# ProPrj_PiezoBuds-final_2024-09-30.net
KiCad netlist of a schematic drawn in EasyEDA Pro
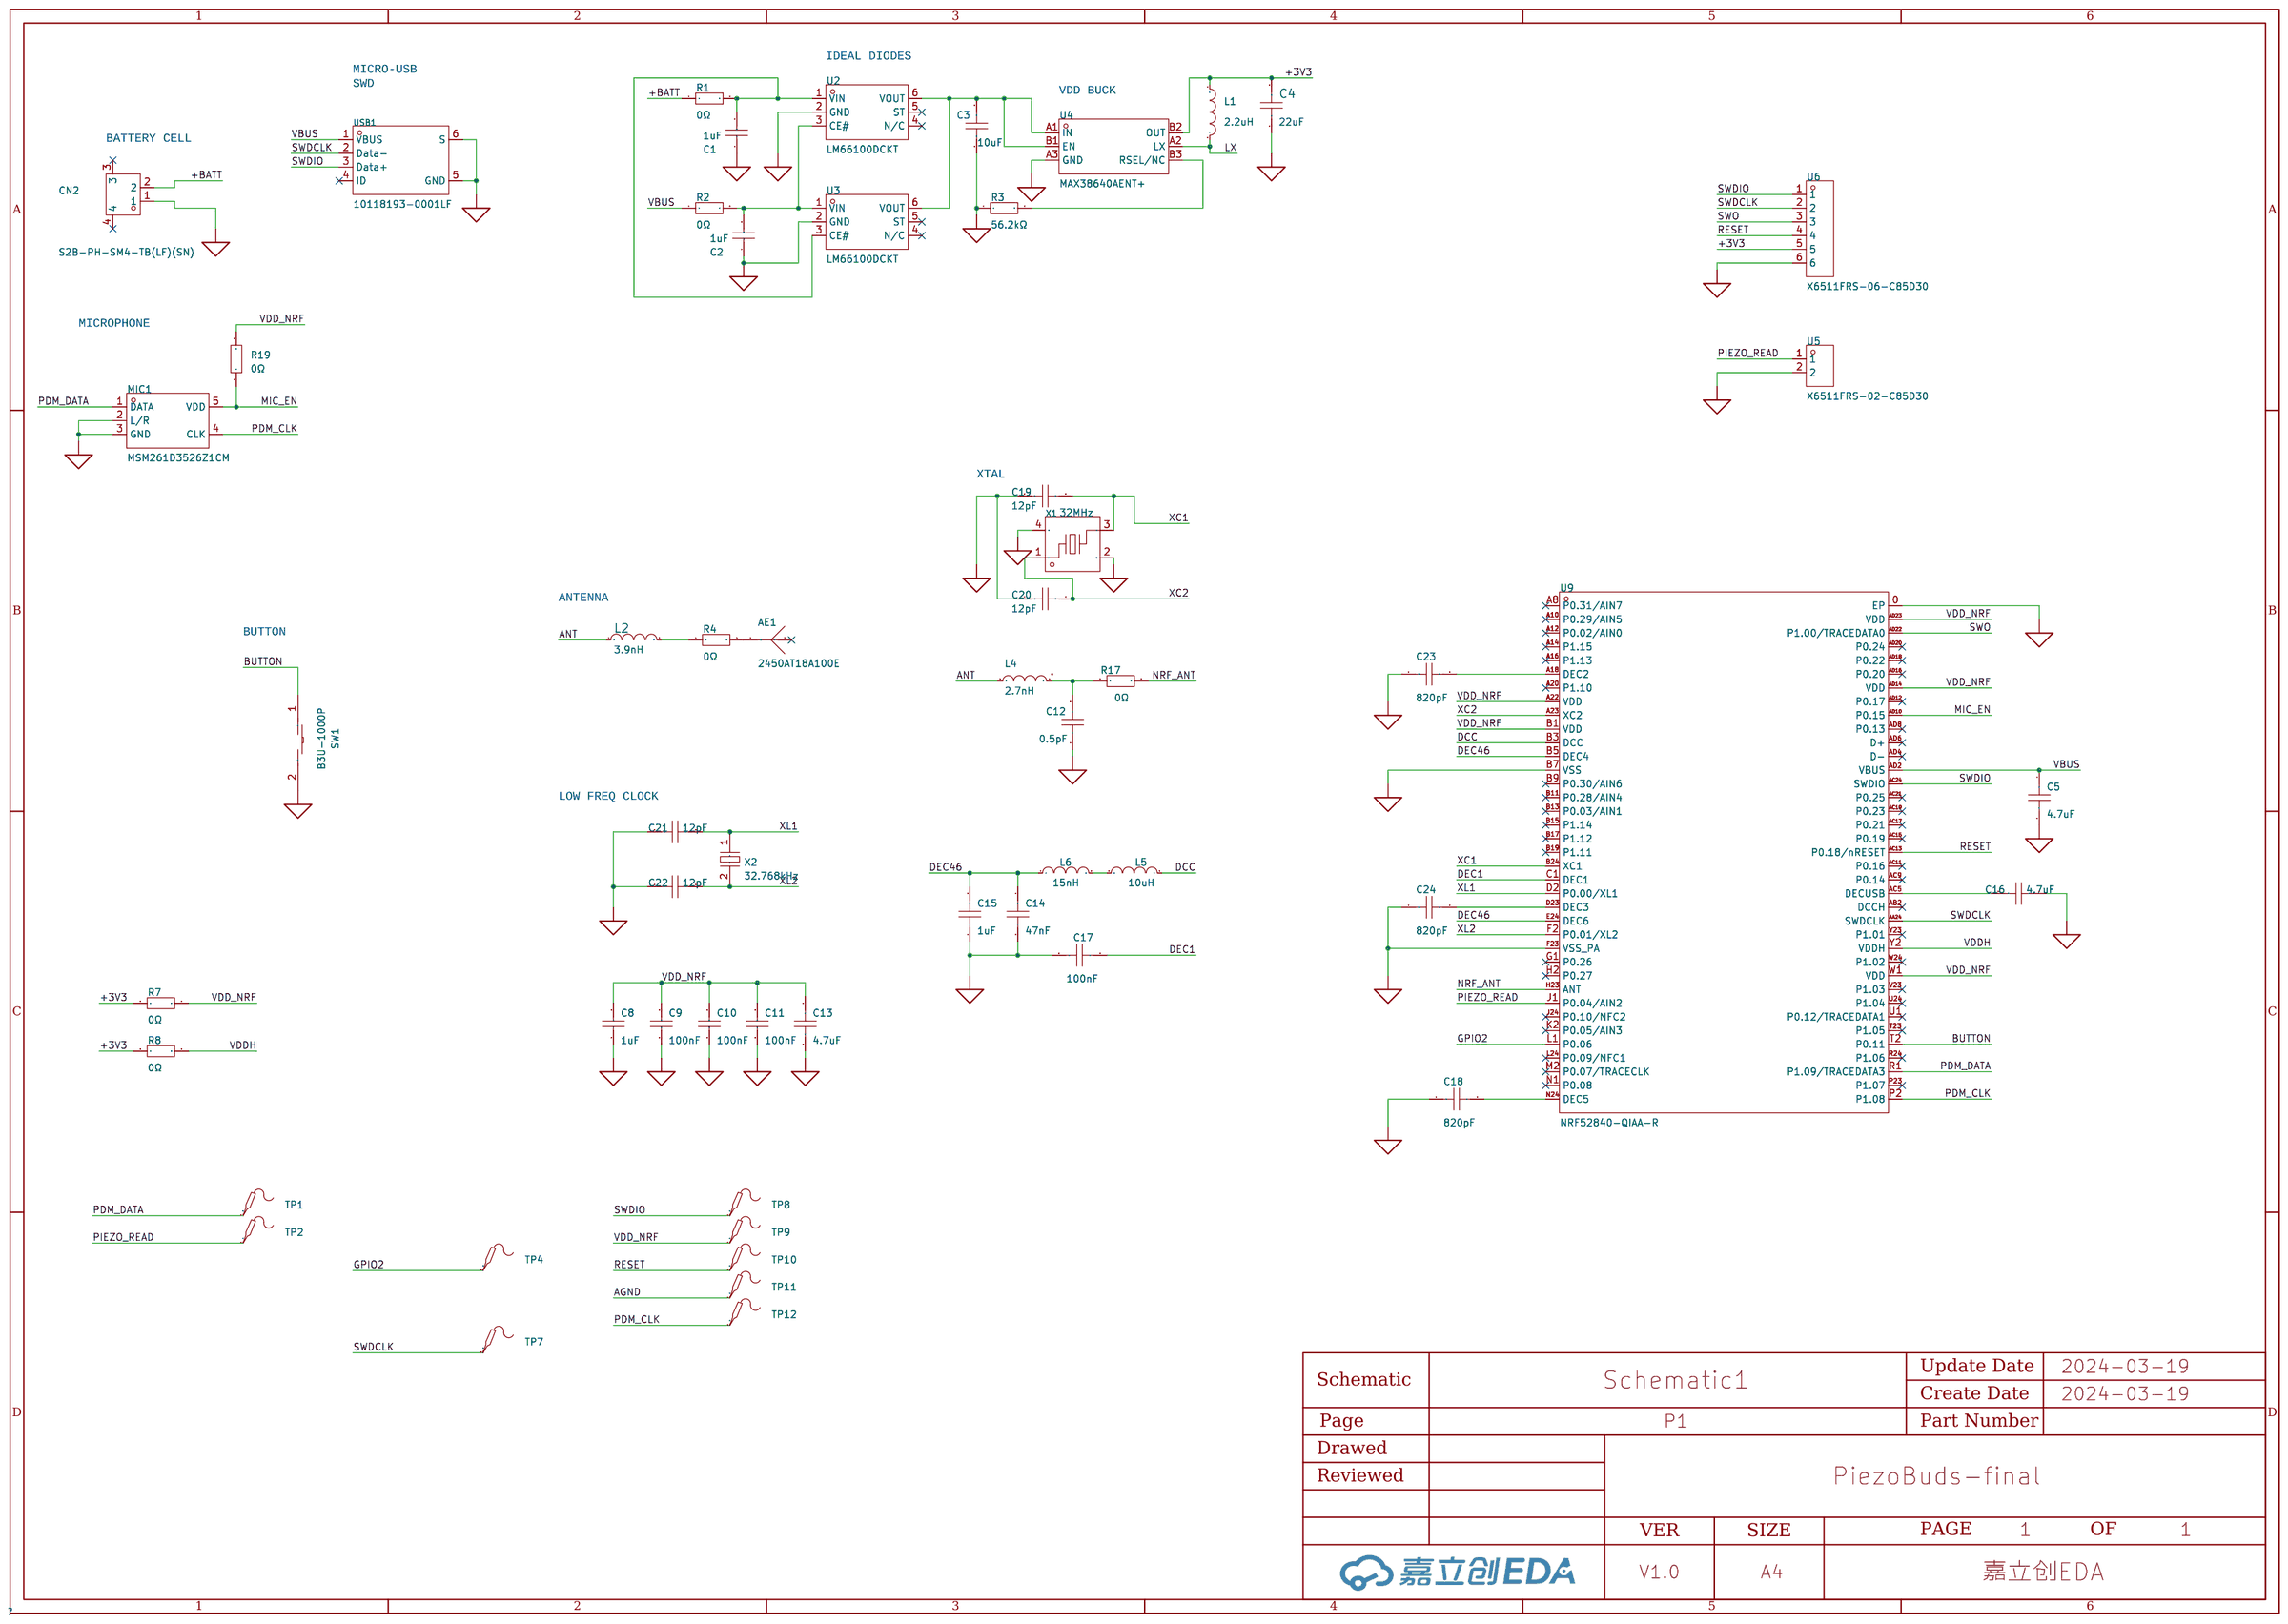
[diagram p0: schematic sheet]

(export (version "E")
  (design (tool "Eeschema 10.0.6"))
  (components
    (comp (ref "AE1")
      (value "2450AT18A100E")
      (footprint "easyedapro:ANT-SMD_L3.2-W1.6")
      (description "天线类型:迷你2.45 GHz天线;中心频点:2.4GHz;带宽:-;峰值增益:0.5dBi;驻波比:-;极化方式:-;阻抗:50Ω;功率容量:2W;")
      (fields (field (name "Manufacturer") "JOHANSON(约翰逊)"))
      (libsource (lib "easyedapro") (part "2450AT18A100E"))
    )
    (comp (ref "C1")
      (value "1uF")
      (footprint "easyedapro:C0402")
      (description "容值:1uF;精度:±10%;额定电压:6.3V;材质(温度系数):X5R;")
      (fields
        (field (name "Manufacturer Part") "CL05A105KQ5NNNC")
        (field (name "Manufacturer") "SAMSUNG(三星)")
      )
      (libsource (lib "easyedapro") (part "CL05A105KQ5NNNC"))
    )
    (comp (ref "C2")
      (value "1uF")
      (footprint "easyedapro:C0402")
      (description "容值:1uF;精度:±10%;额定电压:6.3V;材质(温度系数):X5R;")
      (fields
        (field (name "Manufacturer Part") "CL05A105KQ5NNNC")
        (field (name "Manufacturer") "SAMSUNG(三星)")
      )
      (libsource (lib "easyedapro") (part "CL05A105KQ5NNNC"))
    )
    (comp (ref "C3")
      (value "10uF")
      (footprint "easyedapro:C0402")
      (description "容值:10uF;精度:±20%;额定电压:10V;材质(温度系数):X5R;")
      (fields
        (field (name "Manufacturer Part") "CL05A106MP5NUNC")
        (field (name "Manufacturer") "SAMSUNG(三星)")
      )
      (libsource (lib "easyedapro") (part "CL05A106MP5NUNC_C315248"))
    )
    (comp (ref "C4")
      (value "22uF")
      (footprint "easyedapro:C0402")
      (description "容值:22uF;精度:±20%;额定电压:6.3V;材质(温度系数):X5R;")
      (fields
        (field (name "Manufacturer Part") "GRM155R60J226ME11D")
        (field (name "Manufacturer") "muRata(村田)")
      )
      (libsource (lib "easyedapro") (part "GRM155R60J226ME11D"))
    )
    (comp (ref "C5")
      (value "4.7uF")
      (footprint "easyedapro:C0402")
      (description "容值:4.7uF;精度:±20%;额定电压:4V;材质(温度系数):X6S;")
      (fields (field (name "Manufacturer Part") "C1005X6S0G475M050BC") (field (name "Manufacturer") "TDK"))
      (libsource (lib "easyedapro") (part "C1005X6S0G475M050BC"))
    )
    (comp (ref "C8")
      (value "1uF")
      (footprint "easyedapro:C0402")
      (description "容值:1uF;精度:±10%;额定电压:6.3V;材质(温度系数):X5R;")
      (fields
        (field (name "Manufacturer Part") "CL05A105KQ5NNNC")
        (field (name "Manufacturer") "SAMSUNG(三星)")
      )
      (libsource (lib "easyedapro") (part "CL05A105KQ5NNNC"))
    )
    (comp (ref "C9")
      (value "100nF")
      (footprint "easyedapro:C0201")
      (description "容值:100nF;精度:±10%;额定电压:16V;材质(温度系数):X7S;")
      (fields
        (field (name "Manufacturer Part") "GRM033C71C104KE14D")
        (field (name "Manufacturer") "muRata(村田)")
      )
      (libsource (lib "easyedapro") (part "GRM033C71C104KE14D"))
    )
    (comp (ref "C10")
      (value "100nF")
      (footprint "easyedapro:C0201")
      (description "容值:100nF;精度:±10%;额定电压:16V;材质(温度系数):X7S;")
      (fields
        (field (name "Manufacturer Part") "GRM033C71C104KE14D")
        (field (name "Manufacturer") "muRata(村田)")
      )
      (libsource (lib "easyedapro") (part "GRM033C71C104KE14D"))
    )
    (comp (ref "C11")
      (value "100nF")
      (footprint "easyedapro:C0201")
      (description "容值:100nF;精度:±10%;额定电压:16V;材质(温度系数):X7S;")
      (fields
        (field (name "Manufacturer Part") "GRM033C71C104KE14D")
        (field (name "Manufacturer") "muRata(村田)")
      )
      (libsource (lib "easyedapro") (part "GRM033C71C104KE14D"))
    )
    (comp (ref "C12")
      (value "0.5pF")
      (footprint "easyedapro:C0201")
      (description "容值:0.5pF;额定电压:25V;材质(温度系数):C0G;")
      (fields (field (name "Manufacturer Part") "0201CG0R5B250NT") (field (name "Manufacturer") "FH(风华)"))
      (libsource (lib "easyedapro") (part "0201CG0R5B250NT"))
    )
    (comp (ref "C13")
      (value "4.7uF")
      (footprint "easyedapro:C0402")
      (description "容值:4.7uF;精度:±10%;额定电压:10V;材质(温度系数):X5R;")
      (fields
        (field (name "Manufacturer Part") "CL05A475KP5NRNC")
        (field (name "Manufacturer") "SAMSUNG(三星)")
      )
      (libsource (lib "easyedapro") (part "CL05A475KP5NRNC"))
    )
    (comp (ref "C14")
      (value "47nF")
      (footprint "easyedapro:C0201")
      (description "容值:47nF;精度:±10%;额定电压:6.3V;材质(温度系数):X5R;")
      (fields
        (field (name "Manufacturer Part") "CL03A473KQ3NNNC")
        (field (name "Manufacturer") "SAMSUNG(三星)")
      )
      (libsource (lib "easyedapro") (part "CL03A473KQ3NNNC"))
    )
    (comp (ref "C15")
      (value "1uF")
      (footprint "easyedapro:C0402")
      (description "容值:1uF;精度:±10%;额定电压:6.3V;材质(温度系数):X7R;")
      (fields
        (field (name "Manufacturer Part") "GRM155R70J105KA12D")
        (field (name "Manufacturer") "muRata(村田)")
      )
      (libsource (lib "easyedapro") (part "GRM155R70J105KA12D"))
    )
    (comp (ref "C16")
      (value "4.7uF")
      (footprint "easyedapro:C0402")
      (description "容值:4.7uF;精度:±10%;额定电压:10V;材质(温度系数):X5R;")
      (fields
        (field (name "Manufacturer Part") "CL05A475KP5NRNC")
        (field (name "Manufacturer") "SAMSUNG(三星)")
      )
      (libsource (lib "easyedapro") (part "CL05A475KP5NRNC"))
    )
    (comp (ref "C17")
      (value "100nF")
      (footprint "easyedapro:C0201")
      (description "容值:100nF;精度:±10%;额定电压:6.3V;材质(温度系数):X5R;")
      (fields
        (field (name "Manufacturer Part") "CL03A104KQ3NNNC")
        (field (name "Manufacturer") "SAMSUNG(三星)")
      )
      (libsource (lib "easyedapro") (part "CL03A104KQ3NNNC"))
    )
    (comp (ref "C18")
      (value "820pF")
      (footprint "easyedapro:C0201")
      (description "容值:820pF;精度:±5%;额定电压:25V;材质(温度系数):C0G;")
      (fields
        (field (name "Manufacturer Part") "GRM0335C1E821JA01D")
        (field (name "Manufacturer") "muRata(村田)")
      )
      (libsource (lib "easyedapro") (part "GRM0335C1E821JA01D"))
    )
    (comp (ref "C19")
      (value "12pF")
      (footprint "easyedapro:C0201")
      (description "容值:12pF;精度:±2%;额定电压:25V;材质(温度系数):C0G;")
      (fields
        (field (name "Manufacturer Part") "GRM0335C1E120GA01D")
        (field (name "Manufacturer") "muRata(村田)")
      )
      (libsource (lib "easyedapro") (part "GRM0335C1E120GA01D"))
    )
    (comp (ref "C20")
      (value "12pF")
      (footprint "easyedapro:C0201")
      (description "容值:12pF;精度:±2%;额定电压:25V;材质(温度系数):C0G;")
      (fields
        (field (name "Manufacturer Part") "GRM0335C1E120GA01D")
        (field (name "Manufacturer") "muRata(村田)")
      )
      (libsource (lib "easyedapro") (part "GRM0335C1E120GA01D"))
    )
    (comp (ref "C21")
      (value "12pF")
      (footprint "easyedapro:C0201")
      (description "容值:12pF;精度:±2%;额定电压:25V;材质(温度系数):C0G;")
      (fields
        (field (name "Manufacturer Part") "GRM0335C1E120GA01D")
        (field (name "Manufacturer") "muRata(村田)")
      )
      (libsource (lib "easyedapro") (part "GRM0335C1E120GA01D"))
    )
    (comp (ref "C22")
      (value "12pF")
      (footprint "easyedapro:C0201")
      (description "容值:12pF;精度:±2%;额定电压:25V;材质(温度系数):C0G;")
      (fields
        (field (name "Manufacturer Part") "GRM0335C1E120GA01D")
        (field (name "Manufacturer") "muRata(村田)")
      )
      (libsource (lib "easyedapro") (part "GRM0335C1E120GA01D"))
    )
    (comp (ref "C23")
      (value "820pF")
      (footprint "easyedapro:C0201")
      (description "容值:820pF;精度:±5%;额定电压:25V;材质(温度系数):C0G;")
      (fields
        (field (name "Manufacturer Part") "GRM0335C1E821JA01D")
        (field (name "Manufacturer") "muRata(村田)")
      )
      (libsource (lib "easyedapro") (part "GRM0335C1E821JA01D"))
    )
    (comp (ref "C24")
      (value "820pF")
      (footprint "easyedapro:C0201")
      (description "容值:820pF;精度:±5%;额定电压:25V;材质(温度系数):C0G;")
      (fields
        (field (name "Manufacturer Part") "GRM0335C1E821JA01D")
        (field (name "Manufacturer") "muRata(村田)")
      )
      (libsource (lib "easyedapro") (part "GRM0335C1E821JA01D"))
    )
    (comp (ref "CN2")
      (value "S2B-PH-SM4-TB(LF)(SN)")
      (footprint "easyedapro:CONN-SMD_P2.00_S2B-PH-SM4-TB-LF-SN")
      (fields (field (name "Manufacturer") "JST"))
      (libsource (lib "easyedapro") (part "S2B-PH-SM4-TB(LF)(SN)"))
    )
    (comp (ref "L1")
      (value "2.2uH")
      (footprint "easyedapro:L0603")
      (description "类型:-;电感值:2.2uH;精度:±20%;额定电流:250mA;饱和电流(Isat):-;")
      (fields
        (field (name "Manufacturer Part") "SLM16082R2MIT")
        (field (name "Manufacturer") "Sunltech(韩国顺磁)")
      )
      (libsource (lib "easyedapro") (part "SLM16082R2MIT"))
    )
    (comp (ref "L2")
      (value "3.9nH")
      (footprint "easyedapro:IND-SMD_L1.0-W0.5-2")
      (description "电感值:3.9nH;额定电流:-;饱和电流(Isat):-;直流电阻(DCR):70mΩ;")
      (fields (field (name "Manufacturer Part") "LQW15AN3N9C00D") (field (name "Manufacturer") "muRata(村田)"))
      (libsource (lib "easyedapro") (part "LQW15AN3N9C00D"))
    )
    (comp (ref "L4")
      (value "2.7nH")
      (footprint "easyedapro:L0201-RD")
      (description "电感值:2.7nH;精度:-;额定电流:450mA;饱和电流(Isat):-;直流电阻(DCR):250mΩ;")
      (fields (field (name "Manufacturer Part") "LQP03TG2N7B02D") (field (name "Manufacturer") "muRata(村田)"))
      (libsource (lib "easyedapro") (part "LQP03TG2N7B02D"))
    )
    (comp (ref "L5")
      (value "10uH")
      (footprint "easyedapro:L0603")
      (description "电感值:10uH;精度:±20%;额定电流:300mA;饱和电流(Isat):60mA;直流电阻(DCR):600mΩ;")
      (fields (field (name "Manufacturer Part") "MLZ1608N100LT000") (field (name "Manufacturer") "TDK"))
      (libsource (lib "easyedapro") (part "MLZ1608N100LT000"))
    )
    (comp (ref "L6")
      (value "15nH")
      (footprint "easyedapro:L0201")
      (description "直流电阻(DCR):700mΩ;精度:±5%;电感值:15nH;额定电流:3.8A;饱和电流(Isat):-;")
      (fields (field (name "Manufacturer Part") "LQP03TN15NJ02D") (field (name "Manufacturer") "muRata(村田)"))
      (libsource (lib "easyedapro") (part "LQP03TN15NJ02D"))
    )
    (comp (ref "MIC1")
      (value "MSM261D3526Z1CM")
      (footprint "easyedapro:OCLGA-6_L3.5-W2.7-TL-MSM261D3526Z1CM")
      (description "方向:全指向;灵敏度:-26dB；-25dB;信噪比:62dB；64dB;电流消耗:670uA；290uA;电源电压:1.8V;阻抗:-;")
      (fields (field (name "Manufacturer") "MEMS(敏芯微)"))
      (libsource (lib "easyedapro") (part "MSM261D3526Z1CM"))
    )
    (comp (ref "R1")
      (value "0Ω")
      (footprint "easyedapro:R0201")
      (description "温度系数:-;工作温度范围:-55°C~+155°C;电阻长:-;精度:±5%;电阻直径:-;电阻高:-;电阻宽:-;最大工作电压:25V;电阻类型:厚膜电阻;阻值:0Ω;功率:50mW;")
      (fields (field (name "Manufacturer Part") "RC0201JR-070RL") (field (name "Manufacturer") "YAGEO(国巨)"))
      (libsource (lib "easyedapro") (part "RC0201JR-070RL"))
    )
    (comp (ref "R2")
      (value "0Ω")
      (footprint "easyedapro:R0201")
      (description "温度系数:-;工作温度范围:-55°C~+155°C;电阻长:-;精度:±5%;电阻直径:-;电阻高:-;电阻宽:-;最大工作电压:25V;电阻类型:厚膜电阻;阻值:0Ω;功率:50mW;")
      (fields (field (name "Manufacturer Part") "RC0201JR-070RL") (field (name "Manufacturer") "YAGEO(国巨)"))
      (libsource (lib "easyedapro") (part "RC0201JR-070RL"))
    )
    (comp (ref "R3")
      (value "56.2kΩ")
      (footprint "easyedapro:R0201")
      (description "电阻类型:厚膜电阻;阻值:768kΩ;精度:±1%;功率:50mW;")
      (fields (field (name "Manufacturer Part") "RC0201FR-0756K2L") (field (name "Manufacturer") "YAGEO(国巨)"))
      (libsource (lib "easyedapro") (part "0201WMF7683TCE"))
    )
    (comp (ref "R4")
      (value "0Ω")
      (footprint "easyedapro:R0201")
      (description "温度系数:-;工作温度范围:-55°C~+155°C;电阻长:-;精度:±5%;电阻直径:-;电阻高:-;电阻宽:-;最大工作电压:25V;电阻类型:厚膜电阻;阻值:0Ω;功率:50mW;")
      (fields (field (name "Manufacturer Part") "RC0201JR-070RL") (field (name "Manufacturer") "YAGEO(国巨)"))
      (libsource (lib "easyedapro") (part "RC0201JR-070RL"))
    )
    (comp (ref "R7")
      (value "0Ω")
      (footprint "easyedapro:R0402")
      (description "电阻类型:厚膜电阻;阻值:0Ω;精度:-;功率:62.5mW;")
      (fields (field (name "Manufacturer Part") "RC0402FR-070RL") (field (name "Manufacturer") "YAGEO(国巨)"))
      (libsource (lib "easyedapro") (part "RC0402FR-070RL"))
    )
    (comp (ref "R8")
      (value "0Ω")
      (footprint "easyedapro:R0402")
      (description "电阻类型:厚膜电阻;阻值:0Ω;精度:-;功率:62.5mW;")
      (fields (field (name "Manufacturer Part") "RC0402FR-070RL") (field (name "Manufacturer") "YAGEO(国巨)"))
      (libsource (lib "easyedapro") (part "RC0402FR-070RL"))
    )
    (comp (ref "R17")
      (value "0Ω")
      (footprint "easyedapro:R0201")
      (description "温度系数:-;工作温度范围:-55°C~+155°C;电阻长:-;精度:±5%;电阻直径:-;电阻高:-;电阻宽:-;最大工作电压:25V;电阻类型:厚膜电阻;阻值:0Ω;功率:50mW;")
      (fields (field (name "Manufacturer Part") "RC0201JR-070RL") (field (name "Manufacturer") "YAGEO(国巨)"))
      (libsource (lib "easyedapro") (part "RC0201JR-070RL"))
    )
    (comp (ref "R19")
      (value "0Ω")
      (footprint "easyedapro:R0201")
      (description "温度系数:-;工作温度范围:-55°C~+155°C;电阻长:-;精度:±5%;电阻直径:-;电阻高:-;电阻宽:-;最大工作电压:25V;电阻类型:厚膜电阻;阻值:0Ω;功率:50mW;")
      (fields (field (name "Manufacturer Part") "RC0201JR-070RL") (field (name "Manufacturer") "YAGEO(国巨)"))
      (libsource (lib "easyedapro") (part "RC0201JR-070RL"))
    )
    (comp (ref "SW1")
      (value "B3U-1000P")
      (footprint "easyedapro:KEY-SMD_B3U-1000PM")
      (description "触点电流:50mA;额定电压(DC):12V;电路结构:单刀单掷;安装方式:立贴;带灯:-;机械寿命:-;")
      (fields (field (name "Manufacturer") "OMRON(欧姆龙)"))
      (libsource (lib "easyedapro") (part "B3U-1000P"))
    )
    (comp (ref "TP1")
      (value "~")
      (footprint "easyedapro:Test-Point-0.5mm")
      (description "Test Point 测试点")
      (libsource (lib "easyedapro") (part "Test-Point"))
    )
    (comp (ref "TP2")
      (value "~")
      (footprint "easyedapro:Test-Point-0.5mm")
      (description "Test Point 测试点")
      (libsource (lib "easyedapro") (part "Test-Point"))
    )
    (comp (ref "TP4")
      (value "~")
      (footprint "easyedapro:Test-Point-0.5mm")
      (description "Test Point 测试点")
      (libsource (lib "easyedapro") (part "Test-Point"))
    )
    (comp (ref "TP7")
      (value "~")
      (footprint "easyedapro:Test-Point-0.5mm")
      (description "Test Point 测试点")
      (libsource (lib "easyedapro") (part "Test-Point"))
    )
    (comp (ref "TP8")
      (value "~")
      (footprint "easyedapro:Test-Point-0.5mm")
      (description "Test Point 测试点")
      (libsource (lib "easyedapro") (part "Test-Point"))
    )
    (comp (ref "TP9")
      (value "~")
      (footprint "easyedapro:Test-Point-0.5mm")
      (description "Test Point 测试点")
      (libsource (lib "easyedapro") (part "Test-Point"))
    )
    (comp (ref "TP10")
      (value "~")
      (footprint "easyedapro:Test-Point-0.5mm")
      (description "Test Point 测试点")
      (libsource (lib "easyedapro") (part "Test-Point"))
    )
    (comp (ref "TP11")
      (value "~")
      (footprint "easyedapro:Test-Point-0.5mm")
      (description "Test Point 测试点")
      (libsource (lib "easyedapro") (part "Test-Point"))
    )
    (comp (ref "TP12")
      (value "~")
      (footprint "easyedapro:Test-Point-0.5mm")
      (description "Test Point 测试点")
      (libsource (lib "easyedapro") (part "Test-Point"))
    )
    (comp (ref "U2")
      (value "LM66100DCKT")
      (footprint "easyedapro:SC-70-6_L2.0-W1.3-P0.65-LS2.1-BL")
      (fields (field (name "Manufacturer") "TI(德州仪器)"))
      (libsource (lib "easyedapro") (part "LM66100DCKT"))
    )
    (comp (ref "U3")
      (value "LM66100DCKT")
      (footprint "easyedapro:SC-70-6_L2.0-W1.3-P0.65-LS2.1-BL")
      (fields (field (name "Manufacturer") "TI(德州仪器)"))
      (libsource (lib "easyedapro") (part "LM66100DCKT"))
    )
    (comp (ref "U4")
      (value "MAX38640AENT+")
      (footprint "easyedapro:WLP-6_L1.4-W0.9-R2-C3-P0.40-TL")
      (fields (field (name "Manufacturer") "ADI(亚德诺)"))
      (libsource (lib "easyedapro") (part "MAX38640AENT+"))
    )
    (comp (ref "U5")
      (value "X6511FRS-02-C85D30")
      (footprint "easyedapro:HDR-SMD_2P-P2.54-H-F-L11.5")
      (description "插孔结构:1x2P;间距:2.54mm;安装类型:卧贴;排数:单排;总孔位数:2P;塑高:8.5mm;")
      (fields (field (name "Manufacturer") "XKB Connectivity(中国星坤)"))
      (libsource (lib "easyedapro") (part "X6511FRS-02-C85D30"))
    )
    (comp (ref "U6")
      (value "X6511FRS-06-C85D30")
      (footprint "easyedapro:HDR-SMD_6P-P2.54-H-F-L11.5")
      (description "插孔结构:1x6P;间距:2.54mm;安装类型:卧贴;排数:单排;总孔位数:6P;塑高:8.5mm;")
      (fields (field (name "Manufacturer") "XKB Connectivity(中国星坤)"))
      (libsource (lib "easyedapro") (part "X6511FRS-06-C85D30"))
    )
    (comp (ref "U9")
      (value "NRF52840-QIAA-R")
      (footprint "easyedapro:AQFN-73_L7.0-W7.0-P0.50-BL-EP4.8")
      (fields (field (name "Manufacturer") "NORDIC"))
      (libsource (lib "easyedapro") (part "NRF52840-QIAA-R"))
    )
    (comp (ref "USB1")
      (value "10118193-0001LF")
      (footprint "easyedapro:MICRO-USB-SMD_10118193-0001LF")
      (fields (field (name "Manufacturer") "Amphenol"))
      (libsource (lib "easyedapro") (part "10118193-0001LF"))
    )
    (comp (ref "X1")
      (value "32MHz")
      (footprint "easyedapro:CRYSTAL-SMD_4P-L2.0-W1.6-BL")
      (description "晶振类型:贴片晶振;频率:32MHz;常温频差:±10ppm;外接负载电容:8pF;")
      (fields (field (name "Manufacturer Part") "Q22FA12800025") (field (name "Manufacturer") "EPSON(爱普生)"))
      (libsource (lib "easyedapro") (part "Q22FA12800025"))
    )
    (comp (ref "X2")
      (value "32.768kHz")
      (footprint "easyedapro:CRYSTAL-SMD_L3.2-W1.5-1")
      (description "晶振类型:-;频率:32.768kHz;常温频差:±20ppm;外接负载电容:9pF;")
      (fields
        (field (name "Manufacturer Part") "NX3215SA-32.768K-STD-MUA-9")
        (field (name "Manufacturer") "NDK")
      )
      (libsource (lib "easyedapro") (part "NX3215SA-32.768K-STD-MUA-9"))
    )
  )
  (nets
    (net (code "1") (name "/+3V3") (class "Default")
      (node (ref "C4") (pin "2") (pinfunction "2_2") (pintype "input"))
      (node (ref "L1") (pin "1") (pinfunction "1_1") (pintype "input"))
      (node (ref "R7") (pin "1") (pinfunction "1_1") (pintype "input"))
      (node (ref "R8") (pin "1") (pinfunction "1_1") (pintype "input"))
      (node (ref "U4") (pin "B2") (pinfunction "OUT_B2") (pintype "input"))
      (node (ref "U6") (pin "5") (pinfunction "5_5") (pintype "unspecified"))
    )
    (net (code "2") (name "/+BATT") (class "Default")
      (node (ref "CN2") (pin "2") (pinfunction "2_2") (pintype "unspecified"))
      (node (ref "R1") (pin "1") (pinfunction "1_1") (pintype "input"))
    )
    (net (code "3") (name "/ANT") (class "Default")
      (node (ref "L2") (pin "1") (pinfunction "1_1") (pintype "input"))
      (node (ref "L4") (pin "2") (pinfunction "2_2") (pintype "input"))
    )
    (net (code "4") (name "/BUTTON") (class "Default")
      (node (ref "SW1") (pin "1") (pinfunction "1_1") (pintype "input"))
      (node (ref "U9") (pin "T2") (pinfunction "P0.11_T2") (pintype "unspecified"))
    )
    (net (code "5") (name "/DCC") (class "Default")
      (node (ref "L5") (pin "2") (pinfunction "2_2") (pintype "input"))
      (node (ref "U9") (pin "B3") (pinfunction "DCC_B3") (pintype "unspecified"))
    )
    (net (code "6") (name "/DEC1") (class "Default")
      (node (ref "C17") (pin "1") (pinfunction "1_1") (pintype "input"))
      (node (ref "U9") (pin "C1") (pinfunction "DEC1_C1") (pintype "unspecified"))
    )
    (net (code "7") (name "/DEC46") (class "Default")
      (node (ref "C14") (pin "1") (pinfunction "1_1") (pintype "input"))
      (node (ref "C15") (pin "2") (pinfunction "2_2") (pintype "input"))
      (node (ref "L6") (pin "1") (pinfunction "1_1") (pintype "input"))
      (node (ref "U9") (pin "B5") (pinfunction "DEC4_B5") (pintype "unspecified"))
      (node (ref "U9") (pin "E24") (pinfunction "DEC6_E24") (pintype "unspecified"))
    )
    (net (code "8") (name "/GPIO2") (class "Default")
      (node (ref "TP4") (pin "1") (pinfunction "1_1") (pintype "input"))
      (node (ref "U9") (pin "L1") (pinfunction "P0.06_L1") (pintype "unspecified"))
    )
    (net (code "9") (name "/LX") (class "Default")
      (node (ref "L1") (pin "2") (pinfunction "2_2") (pintype "input"))
      (node (ref "U4") (pin "A2") (pinfunction "LX_A2") (pintype "input"))
    )
    (net (code "10") (name "/MIC_EN") (class "Default")
      (node (ref "MIC1") (pin "5") (pinfunction "VDD_5") (pintype "input"))
      (node (ref "R19") (pin "1") (pinfunction "1_1") (pintype "input"))
      (node (ref "U9") (pin "AD10") (pinfunction "P0.15_AD10") (pintype "unspecified"))
    )
    (net (code "11") (name "/NRF_ANT") (class "Default")
      (node (ref "R17") (pin "2") (pinfunction "2_2") (pintype "input"))
      (node (ref "U9") (pin "H23") (pinfunction "ANT_H23") (pintype "unspecified"))
    )
    (net (code "12") (name "/PDM_CLK") (class "Default")
      (node (ref "MIC1") (pin "4") (pinfunction "CLK_4") (pintype "input"))
      (node (ref "TP12") (pin "1") (pinfunction "1_1") (pintype "input"))
      (node (ref "U9") (pin "P2") (pinfunction "P1.08_P2") (pintype "unspecified"))
    )
    (net (code "13") (name "/PDM_DATA") (class "Default")
      (node (ref "MIC1") (pin "1") (pinfunction "DATA_1") (pintype "input"))
      (node (ref "TP1") (pin "1") (pinfunction "1_1") (pintype "input"))
      (node (ref "U9") (pin "R1") (pinfunction "P1.09/TRACEDATA3_R1") (pintype "unspecified"))
    )
    (net (code "14") (name "/PIEZO_READ") (class "Default")
      (node (ref "TP2") (pin "1") (pinfunction "1_1") (pintype "input"))
      (node (ref "U5") (pin "1") (pinfunction "1_1") (pintype "unspecified"))
      (node (ref "U9") (pin "J1") (pinfunction "P0.04/AIN2_J1") (pintype "unspecified"))
    )
    (net (code "15") (name "/RESET") (class "Default")
      (node (ref "TP10") (pin "1") (pinfunction "1_1") (pintype "input"))
      (node (ref "U6") (pin "4") (pinfunction "4_4") (pintype "unspecified"))
      (node (ref "U9") (pin "AC13") (pinfunction "P0.18/nRESET_AC13") (pintype "unspecified"))
    )
    (net (code "16") (name "/SWDCLK") (class "Default")
      (node (ref "TP7") (pin "1") (pinfunction "1_1") (pintype "input"))
      (node (ref "U6") (pin "2") (pinfunction "2_2") (pintype "unspecified"))
      (node (ref "U9") (pin "AA24") (pinfunction "SWDCLK_AA24") (pintype "unspecified"))
      (node (ref "USB1") (pin "2") (pinfunction "Data-_2") (pintype "input"))
    )
    (net (code "17") (name "/SWDIO") (class "Default")
      (node (ref "TP8") (pin "1") (pinfunction "1_1") (pintype "input"))
      (node (ref "U6") (pin "1") (pinfunction "1_1") (pintype "unspecified"))
      (node (ref "U9") (pin "AC24") (pinfunction "SWDIO_AC24") (pintype "unspecified"))
      (node (ref "USB1") (pin "3") (pinfunction "Data+_3") (pintype "input"))
    )
    (net (code "18") (name "/SWO") (class "Default")
      (node (ref "U6") (pin "3") (pinfunction "3_3") (pintype "unspecified"))
      (node (ref "U9") (pin "AD22") (pinfunction "P1.00/TRACEDATA0_AD22") (pintype "unspecified"))
    )
    (net (code "19") (name "/VBUS") (class "Default")
      (node (ref "C5") (pin "1") (pinfunction "1_1") (pintype "input"))
      (node (ref "R2") (pin "1") (pinfunction "1_1") (pintype "input"))
      (node (ref "U9") (pin "AD2") (pinfunction "VBUS_AD2") (pintype "unspecified"))
      (node (ref "USB1") (pin "1") (pinfunction "VBUS_1") (pintype "input"))
    )
    (net (code "20") (name "/VDDH") (class "Default")
      (node (ref "R8") (pin "2") (pinfunction "2_2") (pintype "input"))
      (node (ref "U9") (pin "Y2") (pinfunction "VDDH_Y2") (pintype "unspecified"))
    )
    (net (code "21") (name "/VDD_NRF") (class "Default")
      (node (ref "C10") (pin "1") (pinfunction "1_1") (pintype "input"))
      (node (ref "C11") (pin "1") (pinfunction "1_1") (pintype "input"))
      (node (ref "C13") (pin "2") (pinfunction "2_2") (pintype "input"))
      (node (ref "C8") (pin "2") (pinfunction "2_2") (pintype "input"))
      (node (ref "C9") (pin "1") (pinfunction "1_1") (pintype "input"))
      (node (ref "R19") (pin "2") (pinfunction "2_2") (pintype "input"))
      (node (ref "R7") (pin "2") (pinfunction "2_2") (pintype "input"))
      (node (ref "TP9") (pin "1") (pinfunction "1_1") (pintype "input"))
      (node (ref "U9") (pin "A22") (pinfunction "VDD_A22") (pintype "unspecified"))
      (node (ref "U9") (pin "AD14") (pinfunction "VDD_AD14") (pintype "unspecified"))
      (node (ref "U9") (pin "AD23") (pinfunction "VDD_AD23") (pintype "unspecified"))
      (node (ref "U9") (pin "B1") (pinfunction "VDD_B1") (pintype "unspecified"))
      (node (ref "U9") (pin "W1") (pinfunction "VDD_W1") (pintype "unspecified"))
    )
    (net (code "22") (name "/XC1") (class "Default")
      (node (ref "C19") (pin "2") (pinfunction "2_2") (pintype "input"))
      (node (ref "U9") (pin "B24") (pinfunction "XC1_B24") (pintype "unspecified"))
      (node (ref "X1") (pin "3") (pinfunction "3_3") (pintype "input"))
    )
    (net (code "23") (name "/XC2") (class "Default")
      (node (ref "C20") (pin "2") (pinfunction "2_2") (pintype "input"))
      (node (ref "U9") (pin "A23") (pinfunction "XC2_A23") (pintype "unspecified"))
      (node (ref "X1") (pin "1") (pinfunction "1_1") (pintype "input"))
    )
    (net (code "24") (name "/XL1") (class "Default")
      (node (ref "C21") (pin "2") (pinfunction "2_2") (pintype "input"))
      (node (ref "U9") (pin "D2") (pinfunction "P0.00/XL1_D2") (pintype "unspecified"))
      (node (ref "X2") (pin "1") (pinfunction "1_1") (pintype "input"))
    )
    (net (code "25") (name "/XL2") (class "Default")
      (node (ref "C22") (pin "2") (pinfunction "2_2") (pintype "input"))
      (node (ref "U9") (pin "F2") (pinfunction "P0.01/XL2_F2") (pintype "unspecified"))
      (node (ref "X2") (pin "2") (pinfunction "2_2") (pintype "input"))
    )
    (net (code "26") (name "AGND") (class "Default")
      (node (ref "C1") (pin "1") (pinfunction "1_1") (pintype "input"))
      (node (ref "C10") (pin "2") (pinfunction "2_2") (pintype "input"))
      (node (ref "C11") (pin "2") (pinfunction "2_2") (pintype "input"))
      (node (ref "C12") (pin "1") (pinfunction "1_1") (pintype "input"))
      (node (ref "C13") (pin "1") (pinfunction "1_1") (pintype "input"))
      (node (ref "C14") (pin "2") (pinfunction "2_2") (pintype "input"))
      (node (ref "C15") (pin "1") (pinfunction "1_1") (pintype "input"))
      (node (ref "C16") (pin "1") (pinfunction "1_1") (pintype "input"))
      (node (ref "C17") (pin "2") (pinfunction "2_2") (pintype "input"))
      (node (ref "C18") (pin "1") (pinfunction "1_1") (pintype "input"))
      (node (ref "C19") (pin "1") (pinfunction "1_1") (pintype "input"))
      (node (ref "C2") (pin "1") (pinfunction "1_1") (pintype "input"))
      (node (ref "C20") (pin "1") (pinfunction "1_1") (pintype "input"))
      (node (ref "C21") (pin "1") (pinfunction "1_1") (pintype "input"))
      (node (ref "C22") (pin "1") (pinfunction "1_1") (pintype "input"))
      (node (ref "C23") (pin "1") (pinfunction "1_1") (pintype "input"))
      (node (ref "C24") (pin "1") (pinfunction "1_1") (pintype "input"))
      (node (ref "C3") (pin "1") (pinfunction "1_1") (pintype "input"))
      (node (ref "C4") (pin "1") (pinfunction "1_1") (pintype "input"))
      (node (ref "C5") (pin "2") (pinfunction "2_2") (pintype "input"))
      (node (ref "C8") (pin "1") (pinfunction "1_1") (pintype "input"))
      (node (ref "C9") (pin "2") (pinfunction "2_2") (pintype "input"))
      (node (ref "CN2") (pin "1") (pinfunction "1_1") (pintype "unspecified"))
      (node (ref "MIC1") (pin "2") (pinfunction "L/R_2") (pintype "input"))
      (node (ref "MIC1") (pin "3") (pinfunction "GND_3") (pintype "input"))
      (node (ref "R3") (pin "1") (pinfunction "1_1") (pintype "input"))
      (node (ref "SW1") (pin "2") (pinfunction "2_2") (pintype "input"))
      (node (ref "TP11") (pin "1") (pinfunction "1_1") (pintype "input"))
      (node (ref "U2") (pin "2") (pinfunction "GND_2") (pintype "input"))
      (node (ref "U3") (pin "2") (pinfunction "GND_2") (pintype "input"))
      (node (ref "U4") (pin "A3") (pinfunction "GND_A3") (pintype "input"))
      (node (ref "U5") (pin "2") (pinfunction "2_2") (pintype "unspecified"))
      (node (ref "U6") (pin "6") (pinfunction "6_6") (pintype "unspecified"))
      (node (ref "U9") (pin "0") (pinfunction "EP_0") (pintype "unspecified"))
      (node (ref "U9") (pin "B7") (pinfunction "VSS_B7") (pintype "unspecified"))
      (node (ref "U9") (pin "F23") (pinfunction "VSS_PA_F23") (pintype "unspecified"))
      (node (ref "USB1") (pin "5") (pinfunction "GND_5") (pintype "input"))
      (node (ref "USB1") (pin "6") (pinfunction "S_6") (pintype "input"))
      (node (ref "X1") (pin "2") (pinfunction "GND_2") (pintype "input"))
      (node (ref "X1") (pin "4") (pinfunction "GND_4") (pintype "input"))
    )
    (net (code "27") (name "Net-(AE1-ANT)") (class "Default")
      (node (ref "AE1") (pin "1") (pinfunction "ANT_1") (pintype "input"))
      (node (ref "R4") (pin "2") (pinfunction "2_2") (pintype "input"))
    )
    (net (code "28") (name "Net-(C12-Pad2)") (class "Default")
      (node (ref "C12") (pin "2") (pinfunction "2_2") (pintype "input"))
      (node (ref "L4") (pin "1") (pinfunction "1_1") (pintype "input"))
      (node (ref "R17") (pin "1") (pinfunction "1_1") (pintype "input"))
    )
    (net (code "29") (name "Net-(L2-Pad2)") (class "Default")
      (node (ref "L2") (pin "2") (pinfunction "2_2") (pintype "input"))
      (node (ref "R4") (pin "1") (pinfunction "1_1") (pintype "input"))
    )
    (net (code "30") (name "Net-(L5-Pad1)") (class "Default")
      (node (ref "L5") (pin "1") (pinfunction "1_1") (pintype "input"))
      (node (ref "L6") (pin "2") (pinfunction "2_2") (pintype "input"))
    )
    (net (code "31") (name "Net-(U2-CE#)") (class "Default")
      (node (ref "C2") (pin "2") (pinfunction "2_2") (pintype "input"))
      (node (ref "R2") (pin "2") (pinfunction "2_2") (pintype "input"))
      (node (ref "U2") (pin "3") (pinfunction "CE#_3") (pintype "input"))
      (node (ref "U3") (pin "1") (pinfunction "VIN_1") (pintype "input"))
    )
    (net (code "32") (name "Net-(U2-VIN)") (class "Default")
      (node (ref "C1") (pin "2") (pinfunction "2_2") (pintype "input"))
      (node (ref "R1") (pin "2") (pinfunction "2_2") (pintype "input"))
      (node (ref "U2") (pin "1") (pinfunction "VIN_1") (pintype "input"))
      (node (ref "U3") (pin "3") (pinfunction "CE#_3") (pintype "input"))
    )
    (net (code "33") (name "Net-(U2-VOUT)") (class "Default")
      (node (ref "C3") (pin "2") (pinfunction "2_2") (pintype "input"))
      (node (ref "U2") (pin "6") (pinfunction "VOUT_6") (pintype "input"))
      (node (ref "U3") (pin "6") (pinfunction "VOUT_6") (pintype "input"))
      (node (ref "U4") (pin "A1") (pinfunction "IN_A1") (pintype "input"))
      (node (ref "U4") (pin "B1") (pinfunction "EN_B1") (pintype "input"))
    )
    (net (code "34") (name "Net-(U4-RSEL{slash}NC)") (class "Default")
      (node (ref "R3") (pin "2") (pinfunction "2_2") (pintype "input"))
      (node (ref "U4") (pin "B3") (pinfunction "RSEL/NC_B3") (pintype "input"))
    )
    (net (code "35") (name "Net-(U9-DEC2)") (class "Default")
      (node (ref "C23") (pin "2") (pinfunction "2_2") (pintype "input"))
      (node (ref "U9") (pin "A18") (pinfunction "DEC2_A18") (pintype "unspecified"))
    )
    (net (code "36") (name "Net-(U9-DEC3)") (class "Default")
      (node (ref "C24") (pin "2") (pinfunction "2_2") (pintype "input"))
      (node (ref "U9") (pin "D23") (pinfunction "DEC3_D23") (pintype "unspecified"))
    )
    (net (code "37") (name "Net-(U9-DEC5)") (class "Default")
      (node (ref "C18") (pin "2") (pinfunction "2_2") (pintype "input"))
      (node (ref "U9") (pin "N24") (pinfunction "DEC5_N24") (pintype "unspecified"))
    )
    (net (code "38") (name "Net-(U9-DECUSB)") (class "Default")
      (node (ref "C16") (pin "2") (pinfunction "2_2") (pintype "input"))
      (node (ref "U9") (pin "AC5") (pinfunction "DECUSB_AC5") (pintype "unspecified"))
    )
    (net (code "39") (name "unconnected-(AE1-Pad2)") (class "Default")
      (node (ref "AE1") (pin "2") (pinfunction "2_2") (pintype "input+no_connect"))
    )
    (net (code "40") (name "unconnected-(CN2-Pad3)") (class "Default")
      (node (ref "CN2") (pin "3") (pinfunction "3_3") (pintype "unspecified+no_connect"))
    )
    (net (code "41") (name "unconnected-(CN2-Pad4)") (class "Default")
      (node (ref "CN2") (pin "4") (pinfunction "4_4") (pintype "unspecified+no_connect"))
    )
    (net (code "42") (name "unconnected-(U2-N{slash}C-Pad4)") (class "Default")
      (node (ref "U2") (pin "4") (pinfunction "N/C_4") (pintype "input+no_connect"))
    )
    (net (code "43") (name "unconnected-(U2-ST-Pad5)") (class "Default")
      (node (ref "U2") (pin "5") (pinfunction "ST_5") (pintype "input+no_connect"))
    )
    (net (code "44") (name "unconnected-(U3-N{slash}C-Pad4)") (class "Default")
      (node (ref "U3") (pin "4") (pinfunction "N/C_4") (pintype "input+no_connect"))
    )
    (net (code "45") (name "unconnected-(U3-ST-Pad5)") (class "Default")
      (node (ref "U3") (pin "5") (pinfunction "ST_5") (pintype "input+no_connect"))
    )
    (net (code "46") (name "unconnected-(U9-D+-PadAD6)") (class "Default")
      (node (ref "U9") (pin "AD6") (pinfunction "D+_AD6") (pintype "unspecified+no_connect"))
    )
    (net (code "47") (name "unconnected-(U9-D--PadAD4)") (class "Default")
      (node (ref "U9") (pin "AD4") (pinfunction "D-_AD4") (pintype "unspecified+no_connect"))
    )
    (net (code "48") (name "unconnected-(U9-DCCH-PadAB2)") (class "Default")
      (node (ref "U9") (pin "AB2") (pinfunction "DCCH_AB2") (pintype "unspecified+no_connect"))
    )
    (net (code "49") (name "unconnected-(U9-P0.02{slash}AIN0-PadA12)") (class "Default")
      (node (ref "U9") (pin "A12") (pinfunction "P0.02/AIN0_A12") (pintype "unspecified+no_connect"))
    )
    (net (code "50") (name "unconnected-(U9-P0.03{slash}AIN1-PadB13)") (class "Default")
      (node (ref "U9") (pin "B13") (pinfunction "P0.03/AIN1_B13") (pintype "unspecified+no_connect"))
    )
    (net (code "51") (name "unconnected-(U9-P0.05{slash}AIN3-PadK2)") (class "Default")
      (node (ref "U9") (pin "K2") (pinfunction "P0.05/AIN3_K2") (pintype "unspecified+no_connect"))
    )
    (net (code "52") (name "unconnected-(U9-P0.07{slash}TRACECLK-PadM2)") (class "Default")
      (node (ref "U9") (pin "M2") (pinfunction "P0.07/TRACECLK_M2") (pintype "unspecified+no_connect"))
    )
    (net (code "53") (name "unconnected-(U9-P0.08-PadN1)") (class "Default")
      (node (ref "U9") (pin "N1") (pinfunction "P0.08_N1") (pintype "unspecified+no_connect"))
    )
    (net (code "54") (name "unconnected-(U9-P0.09{slash}NFC1-PadL24)") (class "Default")
      (node (ref "U9") (pin "L24") (pinfunction "P0.09/NFC1_L24") (pintype "unspecified+no_connect"))
    )
    (net (code "55") (name "unconnected-(U9-P0.10{slash}NFC2-PadJ24)") (class "Default")
      (node (ref "U9") (pin "J24") (pinfunction "P0.10/NFC2_J24") (pintype "unspecified+no_connect"))
    )
    (net (code "56") (name "unconnected-(U9-P0.12{slash}TRACEDATA1-PadU1)") (class "Default")
      (node (ref "U9") (pin "U1") (pinfunction "P0.12/TRACEDATA1_U1") (pintype "unspecified+no_connect"))
    )
    (net (code "57") (name "unconnected-(U9-P0.13-PadAD8)") (class "Default")
      (node (ref "U9") (pin "AD8") (pinfunction "P0.13_AD8") (pintype "unspecified+no_connect"))
    )
    (net (code "58") (name "unconnected-(U9-P0.14-PadAC9)") (class "Default")
      (node (ref "U9") (pin "AC9") (pinfunction "P0.14_AC9") (pintype "unspecified+no_connect"))
    )
    (net (code "59") (name "unconnected-(U9-P0.16-PadAC11)") (class "Default")
      (node (ref "U9") (pin "AC11") (pinfunction "P0.16_AC11") (pintype "unspecified+no_connect"))
    )
    (net (code "60") (name "unconnected-(U9-P0.17-PadAD12)") (class "Default")
      (node (ref "U9") (pin "AD12") (pinfunction "P0.17_AD12") (pintype "unspecified+no_connect"))
    )
    (net (code "61") (name "unconnected-(U9-P0.19-PadAC15)") (class "Default")
      (node (ref "U9") (pin "AC15") (pinfunction "P0.19_AC15") (pintype "unspecified+no_connect"))
    )
    (net (code "62") (name "unconnected-(U9-P0.20-PadAD16)") (class "Default")
      (node (ref "U9") (pin "AD16") (pinfunction "P0.20_AD16") (pintype "unspecified+no_connect"))
    )
    (net (code "63") (name "unconnected-(U9-P0.21-PadAC17)") (class "Default")
      (node (ref "U9") (pin "AC17") (pinfunction "P0.21_AC17") (pintype "unspecified+no_connect"))
    )
    (net (code "64") (name "unconnected-(U9-P0.22-PadAD18)") (class "Default")
      (node (ref "U9") (pin "AD18") (pinfunction "P0.22_AD18") (pintype "unspecified+no_connect"))
    )
    (net (code "65") (name "unconnected-(U9-P0.23-PadAC19)") (class "Default")
      (node (ref "U9") (pin "AC19") (pinfunction "P0.23_AC19") (pintype "unspecified+no_connect"))
    )
    (net (code "66") (name "unconnected-(U9-P0.24-PadAD20)") (class "Default")
      (node (ref "U9") (pin "AD20") (pinfunction "P0.24_AD20") (pintype "unspecified+no_connect"))
    )
    (net (code "67") (name "unconnected-(U9-P0.25-PadAC21)") (class "Default")
      (node (ref "U9") (pin "AC21") (pinfunction "P0.25_AC21") (pintype "unspecified+no_connect"))
    )
    (net (code "68") (name "unconnected-(U9-P0.26-PadG1)") (class "Default")
      (node (ref "U9") (pin "G1") (pinfunction "P0.26_G1") (pintype "unspecified+no_connect"))
    )
    (net (code "69") (name "unconnected-(U9-P0.27-PadH2)") (class "Default")
      (node (ref "U9") (pin "H2") (pinfunction "P0.27_H2") (pintype "unspecified+no_connect"))
    )
    (net (code "70") (name "unconnected-(U9-P0.28{slash}AIN4-PadB11)") (class "Default")
      (node (ref "U9") (pin "B11") (pinfunction "P0.28/AIN4_B11") (pintype "unspecified+no_connect"))
    )
    (net (code "71") (name "unconnected-(U9-P0.29{slash}AIN5-PadA10)") (class "Default")
      (node (ref "U9") (pin "A10") (pinfunction "P0.29/AIN5_A10") (pintype "unspecified+no_connect"))
    )
    (net (code "72") (name "unconnected-(U9-P0.30{slash}AIN6-PadB9)") (class "Default")
      (node (ref "U9") (pin "B9") (pinfunction "P0.30/AIN6_B9") (pintype "unspecified+no_connect"))
    )
    (net (code "73") (name "unconnected-(U9-P0.31{slash}AIN7-PadA8)") (class "Default")
      (node (ref "U9") (pin "A8") (pinfunction "P0.31/AIN7_A8") (pintype "unspecified+no_connect"))
    )
    (net (code "74") (name "unconnected-(U9-P1.01-PadY23)") (class "Default")
      (node (ref "U9") (pin "Y23") (pinfunction "P1.01_Y23") (pintype "unspecified+no_connect"))
    )
    (net (code "75") (name "unconnected-(U9-P1.02-PadW24)") (class "Default")
      (node (ref "U9") (pin "W24") (pinfunction "P1.02_W24") (pintype "unspecified+no_connect"))
    )
    (net (code "76") (name "unconnected-(U9-P1.03-PadV23)") (class "Default")
      (node (ref "U9") (pin "V23") (pinfunction "P1.03_V23") (pintype "unspecified+no_connect"))
    )
    (net (code "77") (name "unconnected-(U9-P1.04-PadU24)") (class "Default")
      (node (ref "U9") (pin "U24") (pinfunction "P1.04_U24") (pintype "unspecified+no_connect"))
    )
    (net (code "78") (name "unconnected-(U9-P1.05-PadT23)") (class "Default")
      (node (ref "U9") (pin "T23") (pinfunction "P1.05_T23") (pintype "unspecified+no_connect"))
    )
    (net (code "79") (name "unconnected-(U9-P1.06-PadR24)") (class "Default")
      (node (ref "U9") (pin "R24") (pinfunction "P1.06_R24") (pintype "unspecified+no_connect"))
    )
    (net (code "80") (name "unconnected-(U9-P1.07-PadP23)") (class "Default")
      (node (ref "U9") (pin "P23") (pinfunction "P1.07_P23") (pintype "unspecified+no_connect"))
    )
    (net (code "81") (name "unconnected-(U9-P1.10-PadA20)") (class "Default")
      (node (ref "U9") (pin "A20") (pinfunction "P1.10_A20") (pintype "unspecified+no_connect"))
    )
    (net (code "82") (name "unconnected-(U9-P1.11-PadB19)") (class "Default")
      (node (ref "U9") (pin "B19") (pinfunction "P1.11_B19") (pintype "unspecified+no_connect"))
    )
    (net (code "83") (name "unconnected-(U9-P1.12-PadB17)") (class "Default")
      (node (ref "U9") (pin "B17") (pinfunction "P1.12_B17") (pintype "unspecified+no_connect"))
    )
    (net (code "84") (name "unconnected-(U9-P1.13-PadA16)") (class "Default")
      (node (ref "U9") (pin "A16") (pinfunction "P1.13_A16") (pintype "unspecified+no_connect"))
    )
    (net (code "85") (name "unconnected-(U9-P1.14-PadB15)") (class "Default")
      (node (ref "U9") (pin "B15") (pinfunction "P1.14_B15") (pintype "unspecified+no_connect"))
    )
    (net (code "86") (name "unconnected-(U9-P1.15-PadA14)") (class "Default")
      (node (ref "U9") (pin "A14") (pinfunction "P1.15_A14") (pintype "unspecified+no_connect"))
    )
    (net (code "87") (name "unconnected-(USB1-ID-Pad4)") (class "Default")
      (node (ref "USB1") (pin "4") (pinfunction "ID_4") (pintype "input+no_connect"))
    )
  )
)
